# 595andMun.net
KiCad netlist of a schematic drawn in Altium Designer
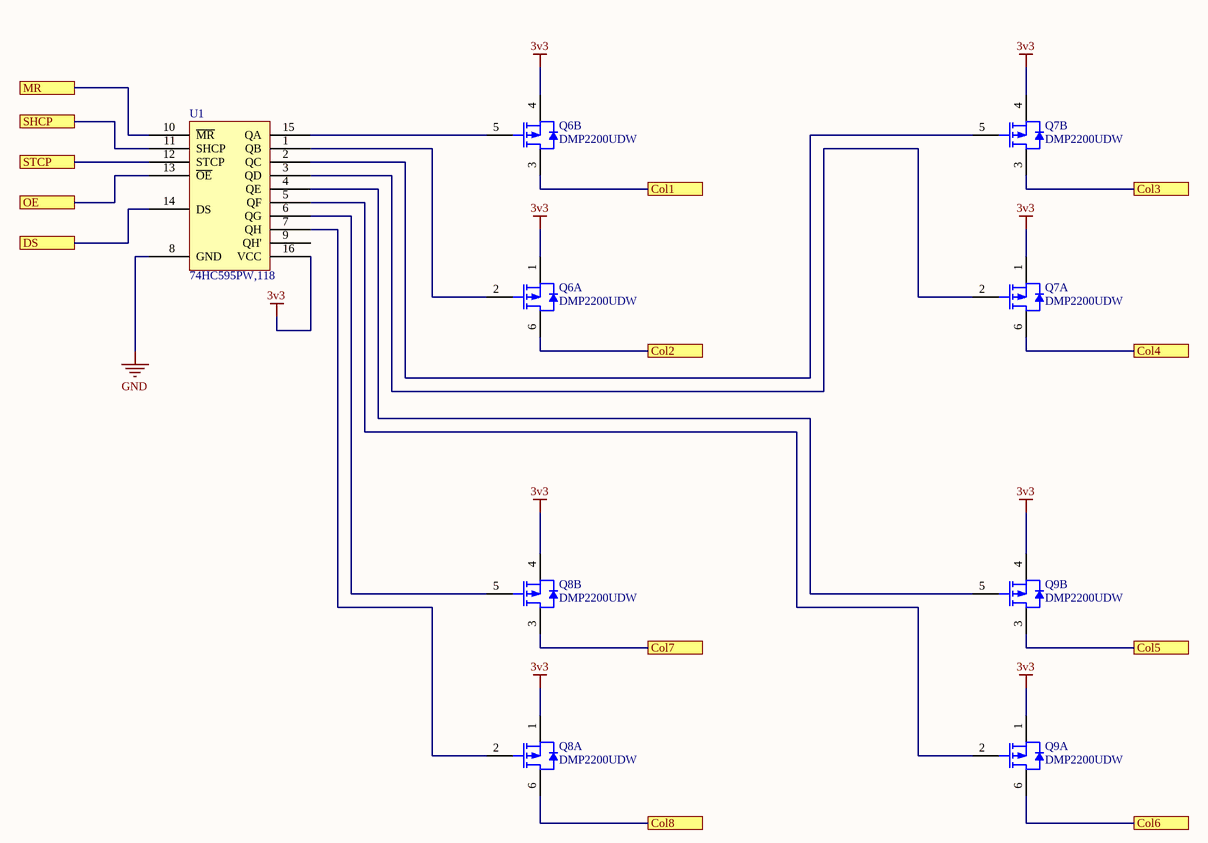
[diagram p0: 595andMun.SchDoc]

(export (version "E")
  (design (tool "Eeschema 10.0.6"))
  (components
    (comp (ref "Q6")
      (value "DMP2200UDW")
      (footprint "DIOD-SOT363-6_V")
      (description "Dual P-Channel Enhancement Mode MOSFET, 50 VDS, -55 to 150 degC, 6-Pin SOT363, RoHS, Tape and Reel")
      (fields (field (name "MANUFACTURER") "DiodesIncorporated"))
      (libsource (lib "Altium Content Vault") (part "PEMOS-SGD-SGD-6"))
    )
    (comp (ref "Q7")
      (value "DMP2200UDW")
      (footprint "DIOD-SOT363-6_V")
      (description "Dual P-Channel Enhancement Mode MOSFET, 50 VDS, -55 to 150 degC, 6-Pin SOT363, RoHS, Tape and Reel")
      (fields (field (name "MANUFACTURER") "DiodesIncorporated"))
      (libsource (lib "Altium Content Vault") (part "PEMOS-SGD-SGD-6"))
    )
    (comp (ref "Q8")
      (value "DMP2200UDW")
      (footprint "DIOD-SOT363-6_V")
      (description "Dual P-Channel Enhancement Mode MOSFET, 50 VDS, -55 to 150 degC, 6-Pin SOT363, RoHS, Tape and Reel")
      (fields (field (name "MANUFACTURER") "DiodesIncorporated"))
      (libsource (lib "Altium Content Vault") (part "PEMOS-SGD-SGD-6"))
    )
    (comp (ref "Q9")
      (value "DMP2200UDW")
      (footprint "DIOD-SOT363-6_V")
      (description "Dual P-Channel Enhancement Mode MOSFET, 50 VDS, -55 to 150 degC, 6-Pin SOT363, RoHS, Tape and Reel")
      (fields (field (name "MANUFACTURER") "DiodesIncorporated"))
      (libsource (lib "Altium Content Vault") (part "PEMOS-SGD-SGD-6"))
    )
    (comp (ref "U1")
      (value "74HC595PW,118")
      (footprint "TSOP65P640X110-16N")
      (description "IC SHIFT REGISTER 8BIT 16TSSOP")
      (libsource (lib "Parts") (part "74HC595PW,118"))
    )
  )
  (nets
    (net (code "1") (name "/Col1") (class "Default")
      (node (ref "Q6") (pin "3") (pinfunction "D_3") (pintype "passive"))
    )
    (net (code "2") (name "/Col2") (class "Default")
      (node (ref "Q6") (pin "6") (pinfunction "D_6") (pintype "passive"))
    )
    (net (code "3") (name "/Col3") (class "Default")
      (node (ref "Q7") (pin "3") (pinfunction "D_3") (pintype "passive"))
    )
    (net (code "4") (name "/Col4") (class "Default")
      (node (ref "Q7") (pin "6") (pinfunction "D_6") (pintype "passive"))
    )
    (net (code "5") (name "/Col5") (class "Default")
      (node (ref "Q9") (pin "3") (pinfunction "D_3") (pintype "passive"))
    )
    (net (code "6") (name "/Col6") (class "Default")
      (node (ref "Q9") (pin "6") (pinfunction "D_6") (pintype "passive"))
    )
    (net (code "7") (name "/Col7") (class "Default")
      (node (ref "Q8") (pin "3") (pinfunction "D_3") (pintype "passive"))
    )
    (net (code "8") (name "/Col8") (class "Default")
      (node (ref "Q8") (pin "6") (pinfunction "D_6") (pintype "passive"))
    )
    (net (code "9") (name "/DS") (class "Default")
      (node (ref "U1") (pin "14") (pinfunction "DS_14") (pintype "passive"))
    )
    (net (code "10") (name "/MR") (class "Default")
      (node (ref "U1") (pin "10") (pinfunction "MR_10") (pintype "passive"))
    )
    (net (code "11") (name "/OE") (class "Default")
      (node (ref "U1") (pin "13") (pinfunction "OE_13") (pintype "passive"))
    )
    (net (code "12") (name "/SHCP") (class "Default")
      (node (ref "U1") (pin "11") (pinfunction "SHCP_11") (pintype "passive"))
    )
    (net (code "13") (name "/STCP") (class "Default")
      (node (ref "U1") (pin "12") (pinfunction "STCP_12") (pintype "passive"))
    )
    (net (code "14") (name "3v3") (class "Default")
      (node (ref "Q6") (pin "1") (pinfunction "S_1") (pintype "passive"))
      (node (ref "Q6") (pin "4") (pinfunction "S_4") (pintype "passive"))
      (node (ref "Q7") (pin "1") (pinfunction "S_1") (pintype "passive"))
      (node (ref "Q7") (pin "4") (pinfunction "S_4") (pintype "passive"))
      (node (ref "Q8") (pin "1") (pinfunction "S_1") (pintype "passive"))
      (node (ref "Q8") (pin "4") (pinfunction "S_4") (pintype "passive"))
      (node (ref "Q9") (pin "1") (pinfunction "S_1") (pintype "passive"))
      (node (ref "Q9") (pin "4") (pinfunction "S_4") (pintype "passive"))
      (node (ref "U1") (pin "16") (pinfunction "VCC_16") (pintype "passive"))
    )
    (net (code "15") (name "GND") (class "Default")
      (node (ref "U1") (pin "8") (pinfunction "GND_8") (pintype "passive"))
    )
    (net (code "16") (name "Net-(Q6A-G)") (class "Default")
      (node (ref "Q6") (pin "2") (pinfunction "G_2") (pintype "passive"))
      (node (ref "U1") (pin "1") (pinfunction "QB_1") (pintype "passive"))
    )
    (net (code "17") (name "Net-(Q6B-G)") (class "Default")
      (node (ref "Q6") (pin "5") (pinfunction "G_5") (pintype "passive"))
      (node (ref "U1") (pin "15") (pinfunction "QA_15") (pintype "passive"))
    )
    (net (code "18") (name "Net-(Q7A-G)") (class "Default")
      (node (ref "Q7") (pin "2") (pinfunction "G_2") (pintype "passive"))
      (node (ref "U1") (pin "3") (pinfunction "QD_3") (pintype "passive"))
    )
    (net (code "19") (name "Net-(Q7B-G)") (class "Default")
      (node (ref "Q7") (pin "5") (pinfunction "G_5") (pintype "passive"))
      (node (ref "U1") (pin "2") (pinfunction "QC_2") (pintype "passive"))
    )
    (net (code "20") (name "Net-(Q8A-G)") (class "Default")
      (node (ref "Q8") (pin "2") (pinfunction "G_2") (pintype "passive"))
      (node (ref "U1") (pin "7") (pinfunction "QH_7") (pintype "passive"))
    )
    (net (code "21") (name "Net-(Q8B-G)") (class "Default")
      (node (ref "Q8") (pin "5") (pinfunction "G_5") (pintype "passive"))
      (node (ref "U1") (pin "6") (pinfunction "QG_6") (pintype "passive"))
    )
    (net (code "22") (name "Net-(Q9A-G)") (class "Default")
      (node (ref "Q9") (pin "2") (pinfunction "G_2") (pintype "passive"))
      (node (ref "U1") (pin "5") (pinfunction "QF_5") (pintype "passive"))
    )
    (net (code "23") (name "Net-(Q9B-G)") (class "Default")
      (node (ref "Q9") (pin "5") (pinfunction "G_5") (pintype "passive"))
      (node (ref "U1") (pin "4") (pinfunction "QE_4") (pintype "passive"))
    )
    (net (code "24") (name "unconnected-(U1-QH'-Pad9)") (class "Default")
      (node (ref "U1") (pin "9") (pinfunction "QH'_9") (pintype "passive"))
    )
  )
)
